# main.net
KiCad netlist of a schematic drawn in EAGLE
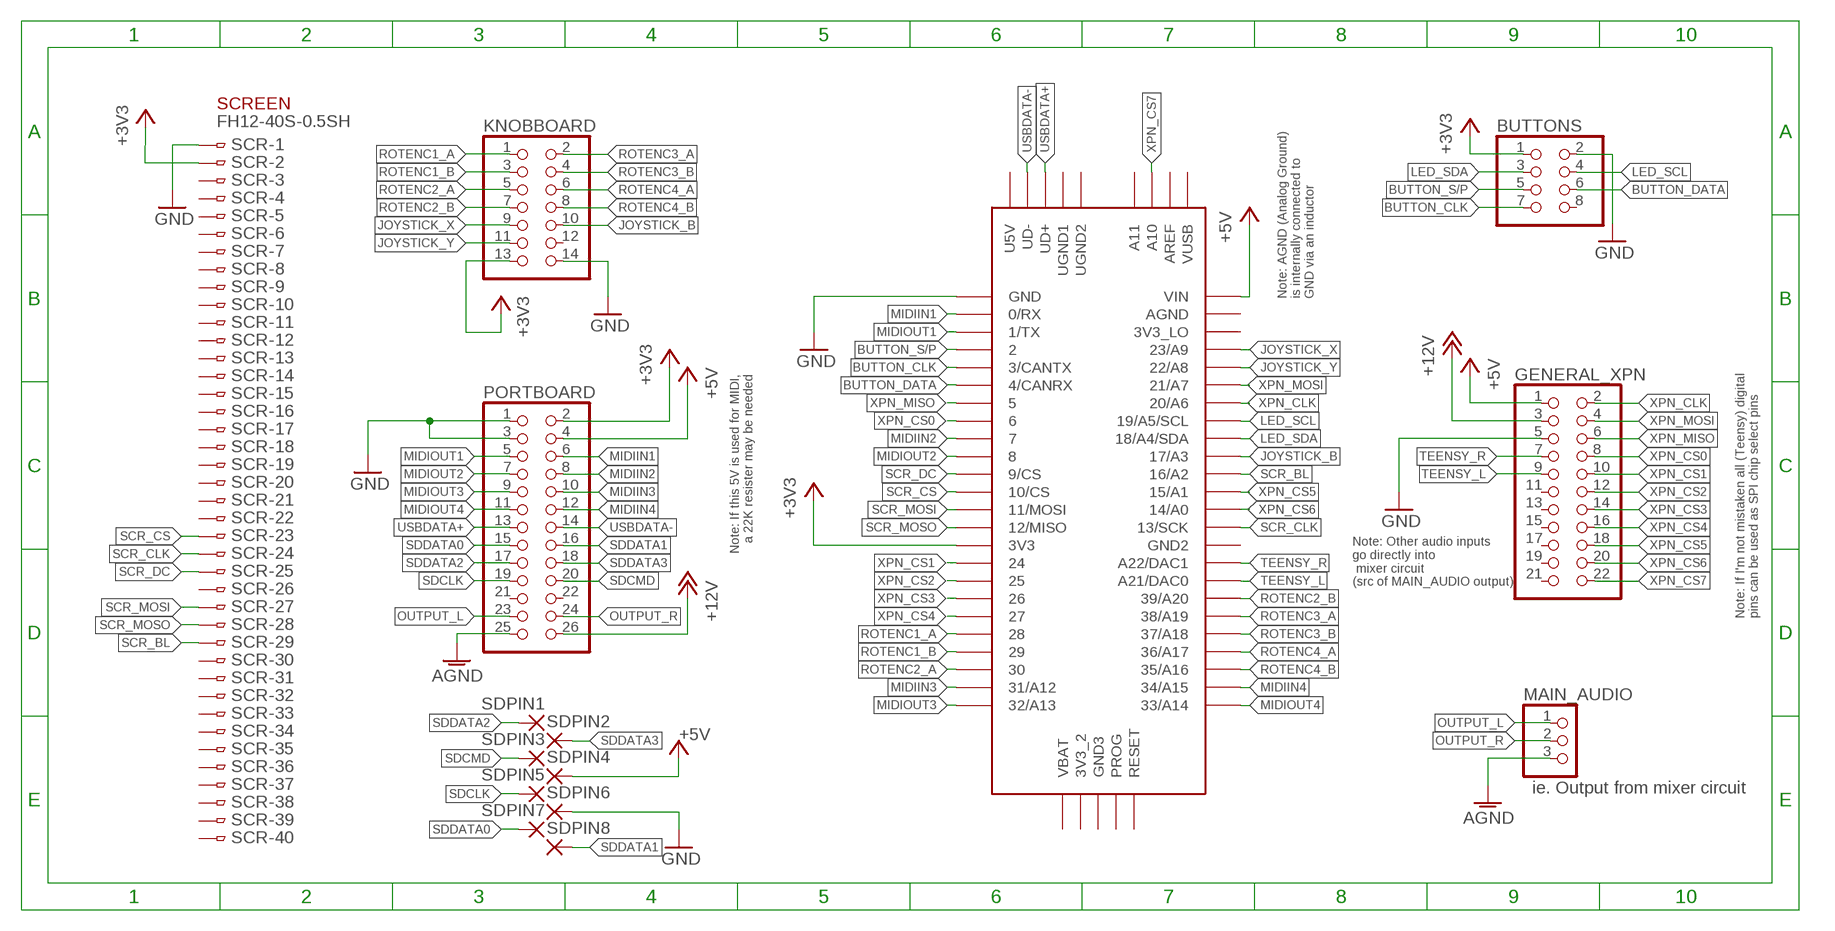
[diagram p0: schematic, sheet 1]

(export (version "E")
  (design (tool "Eeschema 10.0.6"))
  (components
    (comp (ref "BUTTONS")
      (value "PINHD-2X4")
      (footprint "eagle-import:2X04")
      (libsource (lib "eagle-import") (part "PINHD-2X4"))
    )
    (comp (ref "GENERAL_XPN")
      (value "PINHD-2X11")
      (footprint "eagle-import:2X11")
      (libsource (lib "eagle-import") (part "PINHD-2X11"))
    )
    (comp (ref "KNOBBOARD")
      (value "PINHD-2X7")
      (footprint "eagle-import:2X07")
      (libsource (lib "eagle-import") (part "PINHD-2X7"))
    )
    (comp (ref "MAIN_AUDIO")
      (value "PINHD-1X3")
      (footprint "eagle-import:1X03")
      (libsource (lib "eagle-import") (part "PINHD-1X3"))
    )
    (comp (ref "PORTBOARD")
      (value "PINHD-2X13")
      (footprint "eagle-import:2X13")
      (libsource (lib "eagle-import") (part "PINHD-2X13"))
    )
    (comp (ref "SCR")
      (value "FH12-40S-0.5SH")
      (footprint "eagle-import:FH12-40S-0.5SH")
      (fields (field (name "MPN") "FH12-40S-0.5SH(55)"))
      (libsource (lib "eagle-import") (part "FH12-40S-0.5SH"))
    )
    (comp (ref "SDPIN1")
      (value "1,6/0,8")
      (footprint "eagle-import:1,6_0,8")
      (libsource (lib "eagle-import") (part "1,6/0,8"))
    )
    (comp (ref "SDPIN2")
      (value "1,6/0,8")
      (footprint "eagle-import:1,6_0,8")
      (libsource (lib "eagle-import") (part "1,6/0,8"))
    )
    (comp (ref "SDPIN3")
      (value "1,6/0,8")
      (footprint "eagle-import:1,6_0,8")
      (libsource (lib "eagle-import") (part "1,6/0,8"))
    )
    (comp (ref "SDPIN4")
      (value "1,6/0,8")
      (footprint "eagle-import:1,6_0,8")
      (libsource (lib "eagle-import") (part "1,6/0,8"))
    )
    (comp (ref "SDPIN5")
      (value "1,6/0,8")
      (footprint "eagle-import:1,6_0,8")
      (libsource (lib "eagle-import") (part "1,6/0,8"))
    )
    (comp (ref "SDPIN6")
      (value "1,6/0,8")
      (footprint "eagle-import:1,6_0,8")
      (libsource (lib "eagle-import") (part "1,6/0,8"))
    )
    (comp (ref "SDPIN7")
      (value "1,6/0,8")
      (footprint "eagle-import:1,6_0,8")
      (libsource (lib "eagle-import") (part "1,6/0,8"))
    )
    (comp (ref "SDPIN8")
      (value "1,6/0,8")
      (footprint "eagle-import:1,6_0,8")
      (libsource (lib "eagle-import") (part "1,6/0,8"))
    )
    (comp (ref "TEENSY_3.6")
      (value "TEENSY_3.5/3.6")
      (footprint "eagle-import:TEENSY_3.5_3.6")
      (libsource (lib "eagle-import") (part "TEENSY_3.5/3.6"))
    )
  )
  (nets
    (net (code "1") (name "+3V3") (class "Default")
      (node (ref "BUTTONS") (pin "1") (pinfunction "1_1") (pintype "passive"))
      (node (ref "KNOBBOARD") (pin "13") (pinfunction "13_13") (pintype "passive"))
      (node (ref "PORTBOARD") (pin "2") (pinfunction "2_2") (pintype "passive"))
      (node (ref "SCR") (pin "2") (pinfunction "1_2") (pintype "passive"))
      (node (ref "TEENSY_3.6") (pin "3V3") (pinfunction "3V3_3V3") (pintype "bidirectional"))
    )
    (net (code "2") (name "+5V") (class "Default")
      (node (ref "GENERAL_XPN") (pin "1") (pinfunction "1_1") (pintype "passive"))
      (node (ref "PORTBOARD") (pin "4") (pinfunction "4_4") (pintype "passive"))
      (node (ref "SDPIN4") (pin "1") (pinfunction "P_1") (pintype "passive"))
      (node (ref "TEENSY_3.6") (pin "VIN") (pinfunction "VIN_VIN") (pintype "bidirectional"))
    )
    (net (code "3") (name "+12V") (class "Default")
      (node (ref "GENERAL_XPN") (pin "3") (pinfunction "3_3") (pintype "passive"))
      (node (ref "PORTBOARD") (pin "26") (pinfunction "26_26") (pintype "passive"))
    )
    (net (code "4") (name "AGND") (class "Default")
      (node (ref "MAIN_AUDIO") (pin "3") (pinfunction "3_3") (pintype "passive"))
      (node (ref "PORTBOARD") (pin "25") (pinfunction "25_25") (pintype "passive"))
    )
    (net (code "5") (name "BUTTON_CLK") (class "Default")
      (node (ref "BUTTONS") (pin "7") (pinfunction "7_7") (pintype "passive"))
      (node (ref "TEENSY_3.6") (pin "3/CANTX") (pinfunction "3/CANTX_3/CANTX") (pintype "bidirectional"))
    )
    (net (code "6") (name "BUTTON_DATA") (class "Default")
      (node (ref "BUTTONS") (pin "6") (pinfunction "6_6") (pintype "passive"))
      (node (ref "TEENSY_3.6") (pin "4/CANRX") (pinfunction "4/CANRX_4/CANRX") (pintype "bidirectional"))
    )
    (net (code "7") (name "BUTTON_S{slash}P") (class "Default")
      (node (ref "BUTTONS") (pin "5") (pinfunction "5_5") (pintype "passive"))
      (node (ref "TEENSY_3.6") (pin "2") (pinfunction "2_2") (pintype "bidirectional"))
    )
    (net (code "8") (name "GND") (class "Default")
      (node (ref "BUTTONS") (pin "2") (pinfunction "2_2") (pintype "passive"))
      (node (ref "GENERAL_XPN") (pin "5") (pinfunction "5_5") (pintype "passive"))
      (node (ref "KNOBBOARD") (pin "14") (pinfunction "14_14") (pintype "passive"))
      (node (ref "PORTBOARD") (pin "1") (pinfunction "1_1") (pintype "passive"))
      (node (ref "PORTBOARD") (pin "3") (pinfunction "3_3") (pintype "passive"))
      (node (ref "SCR") (pin "1") (pinfunction "1_1") (pintype "passive"))
      (node (ref "SDPIN6") (pin "1") (pinfunction "P_1") (pintype "passive"))
      (node (ref "TEENSY_3.6") (pin "GND") (pinfunction "GND_GND") (pintype "bidirectional"))
    )
    (net (code "9") (name "JOYSTICK_B") (class "Default")
      (node (ref "KNOBBOARD") (pin "10") (pinfunction "10_10") (pintype "passive"))
      (node (ref "TEENSY_3.6") (pin "17/A3") (pinfunction "17/A3_17/A3") (pintype "bidirectional"))
    )
    (net (code "10") (name "JOYSTICK_X") (class "Default")
      (node (ref "KNOBBOARD") (pin "9") (pinfunction "9_9") (pintype "passive"))
      (node (ref "TEENSY_3.6") (pin "23/A9") (pinfunction "23/A9_23/A9") (pintype "bidirectional"))
    )
    (net (code "11") (name "JOYSTICK_Y") (class "Default")
      (node (ref "KNOBBOARD") (pin "11") (pinfunction "11_11") (pintype "passive"))
      (node (ref "TEENSY_3.6") (pin "22/A8") (pinfunction "22/A8_22/A8") (pintype "bidirectional"))
    )
    (net (code "12") (name "LED_SCL") (class "Default")
      (node (ref "BUTTONS") (pin "4") (pinfunction "4_4") (pintype "passive"))
      (node (ref "TEENSY_3.6") (pin "19/A5/SCL") (pinfunction "19/A5/SCL_19/A5/SCL") (pintype "bidirectional"))
    )
    (net (code "13") (name "LED_SDA") (class "Default")
      (node (ref "BUTTONS") (pin "3") (pinfunction "3_3") (pintype "passive"))
      (node (ref "TEENSY_3.6") (pin "18/A4/SDA") (pinfunction "18/A4/SDA_18/A4/SDA") (pintype "bidirectional"))
    )
    (net (code "14") (name "MIDIIN1") (class "Default")
      (node (ref "PORTBOARD") (pin "6") (pinfunction "6_6") (pintype "passive"))
      (node (ref "TEENSY_3.6") (pin "0/RX") (pinfunction "0/RX_0/RX") (pintype "bidirectional"))
    )
    (net (code "15") (name "MIDIIN2") (class "Default")
      (node (ref "PORTBOARD") (pin "8") (pinfunction "8_8") (pintype "passive"))
      (node (ref "TEENSY_3.6") (pin "7") (pinfunction "7_7") (pintype "bidirectional"))
    )
    (net (code "16") (name "MIDIIN3") (class "Default")
      (node (ref "PORTBOARD") (pin "10") (pinfunction "10_10") (pintype "passive"))
      (node (ref "TEENSY_3.6") (pin "31/A12") (pinfunction "31/A12_31/A12") (pintype "bidirectional"))
    )
    (net (code "17") (name "MIDIIN4") (class "Default")
      (node (ref "PORTBOARD") (pin "12") (pinfunction "12_12") (pintype "passive"))
      (node (ref "TEENSY_3.6") (pin "34/A15") (pinfunction "34/A15_34/A15") (pintype "bidirectional"))
    )
    (net (code "18") (name "MIDIOUT1") (class "Default")
      (node (ref "PORTBOARD") (pin "5") (pinfunction "5_5") (pintype "passive"))
      (node (ref "TEENSY_3.6") (pin "1/TX") (pinfunction "1/TX_1/TX") (pintype "bidirectional"))
    )
    (net (code "19") (name "MIDIOUT2") (class "Default")
      (node (ref "PORTBOARD") (pin "7") (pinfunction "7_7") (pintype "passive"))
      (node (ref "TEENSY_3.6") (pin "8") (pinfunction "8_8") (pintype "bidirectional"))
    )
    (net (code "20") (name "MIDIOUT3") (class "Default")
      (node (ref "PORTBOARD") (pin "9") (pinfunction "9_9") (pintype "passive"))
      (node (ref "TEENSY_3.6") (pin "32/A13") (pinfunction "32/A13_32/A13") (pintype "bidirectional"))
    )
    (net (code "21") (name "MIDIOUT4") (class "Default")
      (node (ref "PORTBOARD") (pin "11") (pinfunction "11_11") (pintype "passive"))
      (node (ref "TEENSY_3.6") (pin "33/A14") (pinfunction "33/A14_33/A14") (pintype "bidirectional"))
    )
    (net (code "22") (name "OUTPUT_L") (class "Default")
      (node (ref "MAIN_AUDIO") (pin "1") (pinfunction "1_1") (pintype "passive"))
      (node (ref "PORTBOARD") (pin "23") (pinfunction "23_23") (pintype "passive"))
    )
    (net (code "23") (name "OUTPUT_R") (class "Default")
      (node (ref "MAIN_AUDIO") (pin "2") (pinfunction "2_2") (pintype "passive"))
      (node (ref "PORTBOARD") (pin "24") (pinfunction "24_24") (pintype "passive"))
    )
    (net (code "24") (name "ROTENC1_A") (class "Default")
      (node (ref "KNOBBOARD") (pin "1") (pinfunction "1_1") (pintype "passive"))
      (node (ref "TEENSY_3.6") (pin "28") (pinfunction "28_28") (pintype "bidirectional"))
    )
    (net (code "25") (name "ROTENC1_B") (class "Default")
      (node (ref "KNOBBOARD") (pin "3") (pinfunction "3_3") (pintype "passive"))
      (node (ref "TEENSY_3.6") (pin "29") (pinfunction "29_29") (pintype "bidirectional"))
    )
    (net (code "26") (name "ROTENC2_A") (class "Default")
      (node (ref "KNOBBOARD") (pin "5") (pinfunction "5_5") (pintype "passive"))
      (node (ref "TEENSY_3.6") (pin "30") (pinfunction "30_30") (pintype "bidirectional"))
    )
    (net (code "27") (name "ROTENC2_B") (class "Default")
      (node (ref "KNOBBOARD") (pin "7") (pinfunction "7_7") (pintype "passive"))
      (node (ref "TEENSY_3.6") (pin "39/A20") (pinfunction "39/A20_39/A20") (pintype "bidirectional"))
    )
    (net (code "28") (name "ROTENC3_A") (class "Default")
      (node (ref "KNOBBOARD") (pin "2") (pinfunction "2_2") (pintype "passive"))
      (node (ref "TEENSY_3.6") (pin "38/A19") (pinfunction "38/A19_38/A19") (pintype "bidirectional"))
    )
    (net (code "29") (name "ROTENC3_B") (class "Default")
      (node (ref "KNOBBOARD") (pin "4") (pinfunction "4_4") (pintype "passive"))
      (node (ref "TEENSY_3.6") (pin "37/A18") (pinfunction "37/A18_37/A18") (pintype "bidirectional"))
    )
    (net (code "30") (name "ROTENC4_A") (class "Default")
      (node (ref "KNOBBOARD") (pin "6") (pinfunction "6_6") (pintype "passive"))
      (node (ref "TEENSY_3.6") (pin "36/A17") (pinfunction "36/A17_36/A17") (pintype "bidirectional"))
    )
    (net (code "31") (name "ROTENC4_B") (class "Default")
      (node (ref "KNOBBOARD") (pin "8") (pinfunction "8_8") (pintype "passive"))
      (node (ref "TEENSY_3.6") (pin "35/A16") (pinfunction "35/A16_35/A16") (pintype "bidirectional"))
    )
    (net (code "32") (name "SCR_BL") (class "Default")
      (node (ref "SCR") (pin "29") (pinfunction "1_29") (pintype "passive"))
      (node (ref "TEENSY_3.6") (pin "16/A2") (pinfunction "16/A2_16/A2") (pintype "bidirectional"))
    )
    (net (code "33") (name "SCR_CLK") (class "Default")
      (node (ref "SCR") (pin "24") (pinfunction "1_24") (pintype "passive"))
      (node (ref "TEENSY_3.6") (pin "13/SCK") (pinfunction "13/SCK_13/SCK") (pintype "bidirectional"))
    )
    (net (code "34") (name "SCR_CS") (class "Default")
      (node (ref "SCR") (pin "23") (pinfunction "1_23") (pintype "passive"))
      (node (ref "TEENSY_3.6") (pin "10/CS") (pinfunction "10/CS_10/CS") (pintype "bidirectional"))
    )
    (net (code "35") (name "SCR_DC") (class "Default")
      (node (ref "SCR") (pin "25") (pinfunction "1_25") (pintype "passive"))
      (node (ref "TEENSY_3.6") (pin "9/CS") (pinfunction "9/CS_9/CS") (pintype "bidirectional"))
    )
    (net (code "36") (name "SCR_MOSI") (class "Default")
      (node (ref "SCR") (pin "27") (pinfunction "1_27") (pintype "passive"))
      (node (ref "TEENSY_3.6") (pin "11/MOSI") (pinfunction "11/MOSI_11/MOSI") (pintype "bidirectional"))
    )
    (net (code "37") (name "SCR_MOSO") (class "Default")
      (node (ref "SCR") (pin "28") (pinfunction "1_28") (pintype "passive"))
      (node (ref "TEENSY_3.6") (pin "12/MISO") (pinfunction "12/MISO_12/MISO") (pintype "bidirectional"))
    )
    (net (code "38") (name "SDCLK") (class "Default")
      (node (ref "PORTBOARD") (pin "19") (pinfunction "19_19") (pintype "passive"))
      (node (ref "SDPIN5") (pin "1") (pinfunction "P_1") (pintype "passive"))
    )
    (net (code "39") (name "SDCMD") (class "Default")
      (node (ref "PORTBOARD") (pin "20") (pinfunction "20_20") (pintype "passive"))
      (node (ref "SDPIN3") (pin "1") (pinfunction "P_1") (pintype "passive"))
    )
    (net (code "40") (name "SDDATA0") (class "Default")
      (node (ref "PORTBOARD") (pin "15") (pinfunction "15_15") (pintype "passive"))
      (node (ref "SDPIN7") (pin "1") (pinfunction "P_1") (pintype "passive"))
    )
    (net (code "41") (name "SDDATA1") (class "Default")
      (node (ref "PORTBOARD") (pin "16") (pinfunction "16_16") (pintype "passive"))
      (node (ref "SDPIN8") (pin "1") (pinfunction "P_1") (pintype "passive"))
    )
    (net (code "42") (name "SDDATA2") (class "Default")
      (node (ref "PORTBOARD") (pin "17") (pinfunction "17_17") (pintype "passive"))
      (node (ref "SDPIN1") (pin "1") (pinfunction "P_1") (pintype "passive"))
    )
    (net (code "43") (name "SDDATA3") (class "Default")
      (node (ref "PORTBOARD") (pin "18") (pinfunction "18_18") (pintype "passive"))
      (node (ref "SDPIN2") (pin "1") (pinfunction "P_1") (pintype "passive"))
    )
    (net (code "44") (name "TEENSY_L") (class "Default")
      (node (ref "GENERAL_XPN") (pin "9") (pinfunction "9_9") (pintype "passive"))
      (node (ref "TEENSY_3.6") (pin "21/DAC0") (pinfunction "A21/DAC0_21/DAC0") (pintype "bidirectional"))
    )
    (net (code "45") (name "TEENSY_R") (class "Default")
      (node (ref "GENERAL_XPN") (pin "7") (pinfunction "7_7") (pintype "passive"))
      (node (ref "TEENSY_3.6") (pin "A22/DAC1") (pinfunction "A22/DAC1_A22/DAC1") (pintype "bidirectional"))
    )
    (net (code "46") (name "USBDATA+") (class "Default")
      (node (ref "PORTBOARD") (pin "13") (pinfunction "13_13") (pintype "passive"))
      (node (ref "TEENSY_3.6") (pin "UD+") (pinfunction "UD+_UD+") (pintype "bidirectional"))
    )
    (net (code "47") (name "USBDATA-") (class "Default")
      (node (ref "PORTBOARD") (pin "14") (pinfunction "14_14") (pintype "passive"))
      (node (ref "TEENSY_3.6") (pin "UD-") (pinfunction "UD-_UD-") (pintype "bidirectional"))
    )
    (net (code "48") (name "XPN_CLK") (class "Default")
      (node (ref "GENERAL_XPN") (pin "2") (pinfunction "2_2") (pintype "passive"))
      (node (ref "TEENSY_3.6") (pin "20/A6") (pinfunction "20/A6_20/A6") (pintype "bidirectional"))
    )
    (net (code "49") (name "XPN_CS0") (class "Default")
      (node (ref "GENERAL_XPN") (pin "8") (pinfunction "8_8") (pintype "passive"))
      (node (ref "TEENSY_3.6") (pin "6") (pinfunction "6_6") (pintype "bidirectional"))
    )
    (net (code "50") (name "XPN_CS1") (class "Default")
      (node (ref "GENERAL_XPN") (pin "10") (pinfunction "10_10") (pintype "passive"))
      (node (ref "TEENSY_3.6") (pin "24") (pinfunction "24_24") (pintype "bidirectional"))
    )
    (net (code "51") (name "XPN_CS2") (class "Default")
      (node (ref "GENERAL_XPN") (pin "12") (pinfunction "12_12") (pintype "passive"))
      (node (ref "TEENSY_3.6") (pin "25") (pinfunction "25_25") (pintype "bidirectional"))
    )
    (net (code "52") (name "XPN_CS3") (class "Default")
      (node (ref "GENERAL_XPN") (pin "14") (pinfunction "14_14") (pintype "passive"))
      (node (ref "TEENSY_3.6") (pin "26") (pinfunction "26_26") (pintype "bidirectional"))
    )
    (net (code "53") (name "XPN_CS4") (class "Default")
      (node (ref "GENERAL_XPN") (pin "16") (pinfunction "16_16") (pintype "passive"))
      (node (ref "TEENSY_3.6") (pin "27") (pinfunction "27_27") (pintype "bidirectional"))
    )
    (net (code "54") (name "XPN_CS5") (class "Default")
      (node (ref "GENERAL_XPN") (pin "18") (pinfunction "18_18") (pintype "passive"))
      (node (ref "TEENSY_3.6") (pin "15/A1") (pinfunction "15/A1_15/A1") (pintype "bidirectional"))
    )
    (net (code "55") (name "XPN_CS6") (class "Default")
      (node (ref "GENERAL_XPN") (pin "20") (pinfunction "20_20") (pintype "passive"))
      (node (ref "TEENSY_3.6") (pin "14/A0") (pinfunction "14/A0_14/A0") (pintype "bidirectional"))
    )
    (net (code "56") (name "XPN_CS7") (class "Default")
      (node (ref "GENERAL_XPN") (pin "22") (pinfunction "22_22") (pintype "passive"))
      (node (ref "TEENSY_3.6") (pin "A10") (pinfunction "A10_A10") (pintype "bidirectional"))
    )
    (net (code "57") (name "XPN_MISO") (class "Default")
      (node (ref "GENERAL_XPN") (pin "6") (pinfunction "6_6") (pintype "passive"))
      (node (ref "TEENSY_3.6") (pin "5") (pinfunction "5_5") (pintype "bidirectional"))
    )
    (net (code "58") (name "XPN_MOSI") (class "Default")
      (node (ref "GENERAL_XPN") (pin "4") (pinfunction "4_4") (pintype "passive"))
      (node (ref "TEENSY_3.6") (pin "21/A7") (pinfunction "21/A7_21/A7") (pintype "bidirectional"))
    )
    (net (code "59") (name "unconnected-(BUTTONS-Pad8)") (class "Default")
      (node (ref "BUTTONS") (pin "8") (pinfunction "8_8") (pintype "passive"))
    )
    (net (code "60") (name "unconnected-(GENERAL_XPN-Pad11)") (class "Default")
      (node (ref "GENERAL_XPN") (pin "11") (pinfunction "11_11") (pintype "passive"))
    )
    (net (code "61") (name "unconnected-(GENERAL_XPN-Pad13)") (class "Default")
      (node (ref "GENERAL_XPN") (pin "13") (pinfunction "13_13") (pintype "passive"))
    )
    (net (code "62") (name "unconnected-(GENERAL_XPN-Pad15)") (class "Default")
      (node (ref "GENERAL_XPN") (pin "15") (pinfunction "15_15") (pintype "passive"))
    )
    (net (code "63") (name "unconnected-(GENERAL_XPN-Pad17)") (class "Default")
      (node (ref "GENERAL_XPN") (pin "17") (pinfunction "17_17") (pintype "passive"))
    )
    (net (code "64") (name "unconnected-(GENERAL_XPN-Pad19)") (class "Default")
      (node (ref "GENERAL_XPN") (pin "19") (pinfunction "19_19") (pintype "passive"))
    )
    (net (code "65") (name "unconnected-(GENERAL_XPN-Pad21)") (class "Default")
      (node (ref "GENERAL_XPN") (pin "21") (pinfunction "21_21") (pintype "passive"))
    )
    (net (code "66") (name "unconnected-(KNOBBOARD-Pad12)") (class "Default")
      (node (ref "KNOBBOARD") (pin "12") (pinfunction "12_12") (pintype "passive"))
    )
    (net (code "67") (name "unconnected-(PORTBOARD-Pad21)") (class "Default")
      (node (ref "PORTBOARD") (pin "21") (pinfunction "21_21") (pintype "passive"))
    )
    (net (code "68") (name "unconnected-(PORTBOARD-Pad22)") (class "Default")
      (node (ref "PORTBOARD") (pin "22") (pinfunction "22_22") (pintype "passive"))
    )
    (net (code "69") (name "unconnected-(SCRAA-1-Pad33)") (class "Default")
      (node (ref "SCR") (pin "33") (pinfunction "1_33") (pintype "passive"))
    )
    (net (code "70") (name "unconnected-(SCRAB-1-Pad34)") (class "Default")
      (node (ref "SCR") (pin "34") (pinfunction "1_34") (pintype "passive"))
    )
    (net (code "71") (name "unconnected-(SCRAC-1-Pad35)") (class "Default")
      (node (ref "SCR") (pin "35") (pinfunction "1_35") (pintype "passive"))
    )
    (net (code "72") (name "unconnected-(SCRAD-1-Pad36)") (class "Default")
      (node (ref "SCR") (pin "36") (pinfunction "1_36") (pintype "passive"))
    )
    (net (code "73") (name "unconnected-(SCRAE-1-Pad37)") (class "Default")
      (node (ref "SCR") (pin "37") (pinfunction "1_37") (pintype "passive"))
    )
    (net (code "74") (name "unconnected-(SCRAF-1-Pad38)") (class "Default")
      (node (ref "SCR") (pin "38") (pinfunction "1_38") (pintype "passive"))
    )
    (net (code "75") (name "unconnected-(SCRAG-1-Pad39)") (class "Default")
      (node (ref "SCR") (pin "39") (pinfunction "1_39") (pintype "passive"))
    )
    (net (code "76") (name "unconnected-(SCRAH-1-Pad4)") (class "Default")
      (node (ref "SCR") (pin "4") (pinfunction "1_4") (pintype "passive"))
    )
    (net (code "77") (name "unconnected-(SCRAI-1-Pad40)") (class "Default")
      (node (ref "SCR") (pin "40") (pinfunction "1_40") (pintype "passive"))
    )
    (net (code "78") (name "unconnected-(SCRAJ-1-Pad5)") (class "Default")
      (node (ref "SCR") (pin "5") (pinfunction "1_5") (pintype "passive"))
    )
    (net (code "79") (name "unconnected-(SCRAK-1-Pad6)") (class "Default")
      (node (ref "SCR") (pin "6") (pinfunction "1_6") (pintype "passive"))
    )
    (net (code "80") (name "unconnected-(SCRAL-1-Pad7)") (class "Default")
      (node (ref "SCR") (pin "7") (pinfunction "1_7") (pintype "passive"))
    )
    (net (code "81") (name "unconnected-(SCRAM-1-Pad8)") (class "Default")
      (node (ref "SCR") (pin "8") (pinfunction "1_8") (pintype "passive"))
    )
    (net (code "82") (name "unconnected-(SCRAN-1-Pad9)") (class "Default")
      (node (ref "SCR") (pin "9") (pinfunction "1_9") (pintype "passive"))
    )
    (net (code "83") (name "unconnected-(SCRB-1-Pad10)") (class "Default")
      (node (ref "SCR") (pin "10") (pinfunction "1_10") (pintype "passive"))
    )
    (net (code "84") (name "unconnected-(SCRC-1-Pad11)") (class "Default")
      (node (ref "SCR") (pin "11") (pinfunction "1_11") (pintype "passive"))
    )
    (net (code "85") (name "unconnected-(SCRD-1-Pad12)") (class "Default")
      (node (ref "SCR") (pin "12") (pinfunction "1_12") (pintype "passive"))
    )
    (net (code "86") (name "unconnected-(SCRE-1-Pad13)") (class "Default")
      (node (ref "SCR") (pin "13") (pinfunction "1_13") (pintype "passive"))
    )
    (net (code "87") (name "unconnected-(SCRF-1-Pad14)") (class "Default")
      (node (ref "SCR") (pin "14") (pinfunction "1_14") (pintype "passive"))
    )
    (net (code "88") (name "unconnected-(SCRG-1-Pad15)") (class "Default")
      (node (ref "SCR") (pin "15") (pinfunction "1_15") (pintype "passive"))
    )
    (net (code "89") (name "unconnected-(SCRH-1-Pad16)") (class "Default")
      (node (ref "SCR") (pin "16") (pinfunction "1_16") (pintype "passive"))
    )
    (net (code "90") (name "unconnected-(SCRI-1-Pad17)") (class "Default")
      (node (ref "SCR") (pin "17") (pinfunction "1_17") (pintype "passive"))
    )
    (net (code "91") (name "unconnected-(SCRJ-1-Pad18)") (class "Default")
      (node (ref "SCR") (pin "18") (pinfunction "1_18") (pintype "passive"))
    )
    (net (code "92") (name "unconnected-(SCRK-1-Pad19)") (class "Default")
      (node (ref "SCR") (pin "19") (pinfunction "1_19") (pintype "passive"))
    )
    (net (code "93") (name "unconnected-(SCRM-1-Pad20)") (class "Default")
      (node (ref "SCR") (pin "20") (pinfunction "1_20") (pintype "passive"))
    )
    (net (code "94") (name "unconnected-(SCRN-1-Pad21)") (class "Default")
      (node (ref "SCR") (pin "21") (pinfunction "1_21") (pintype "passive"))
    )
    (net (code "95") (name "unconnected-(SCRO-1-Pad22)") (class "Default")
      (node (ref "SCR") (pin "22") (pinfunction "1_22") (pintype "passive"))
    )
    (net (code "96") (name "unconnected-(SCRS-1-Pad26)") (class "Default")
      (node (ref "SCR") (pin "26") (pinfunction "1_26") (pintype "passive"))
    )
    (net (code "97") (name "unconnected-(SCRW-1-Pad3)") (class "Default")
      (node (ref "SCR") (pin "3") (pinfunction "1_3") (pintype "passive"))
    )
    (net (code "98") (name "unconnected-(SCRX-1-Pad30)") (class "Default")
      (node (ref "SCR") (pin "30") (pinfunction "1_30") (pintype "passive"))
    )
    (net (code "99") (name "unconnected-(SCRY-1-Pad31)") (class "Default")
      (node (ref "SCR") (pin "31") (pinfunction "1_31") (pintype "passive"))
    )
    (net (code "100") (name "unconnected-(SCRZ-1-Pad32)") (class "Default")
      (node (ref "SCR") (pin "32") (pinfunction "1_32") (pintype "passive"))
    )
    (net (code "101") (name "unconnected-(TEENSY_3.6-Pad3V3_2)") (class "Default")
      (node (ref "TEENSY_3.6") (pin "3V3_2") (pinfunction "3V3_2_3V3_2") (pintype "bidirectional"))
    )
    (net (code "102") (name "unconnected-(TEENSY_3.6-Pad3V3_LO)") (class "Default")
      (node (ref "TEENSY_3.6") (pin "3V3_LO") (pinfunction "3V3_LO_3V3_LO") (pintype "bidirectional"))
    )
    (net (code "103") (name "unconnected-(TEENSY_3.6-PadA11)") (class "Default")
      (node (ref "TEENSY_3.6") (pin "A11") (pinfunction "A11_A11") (pintype "bidirectional"))
    )
    (net (code "104") (name "unconnected-(TEENSY_3.6-PadAGND)") (class "Default")
      (node (ref "TEENSY_3.6") (pin "AGND") (pinfunction "AGND_AGND") (pintype "bidirectional"))
    )
    (net (code "105") (name "unconnected-(TEENSY_3.6-PadAREF)") (class "Default")
      (node (ref "TEENSY_3.6") (pin "AREF") (pinfunction "AREF_AREF") (pintype "bidirectional"))
    )
    (net (code "106") (name "unconnected-(TEENSY_3.6-PadGND2)") (class "Default")
      (node (ref "TEENSY_3.6") (pin "GND2") (pinfunction "GND2_GND2") (pintype "bidirectional"))
    )
    (net (code "107") (name "unconnected-(TEENSY_3.6-PadGND3)") (class "Default")
      (node (ref "TEENSY_3.6") (pin "GND3") (pinfunction "GND3_GND3") (pintype "bidirectional"))
    )
    (net (code "108") (name "unconnected-(TEENSY_3.6-PadPROG)") (class "Default")
      (node (ref "TEENSY_3.6") (pin "PROG") (pinfunction "PROG_PROG") (pintype "bidirectional"))
    )
    (net (code "109") (name "unconnected-(TEENSY_3.6-PadRESET)") (class "Default")
      (node (ref "TEENSY_3.6") (pin "RESET") (pinfunction "RESET_RESET") (pintype "bidirectional"))
    )
    (net (code "110") (name "unconnected-(TEENSY_3.6-PadU5V)") (class "Default")
      (node (ref "TEENSY_3.6") (pin "U5V") (pinfunction "U5V_U5V") (pintype "bidirectional"))
    )
    (net (code "111") (name "unconnected-(TEENSY_3.6-PadUGND1)") (class "Default")
      (node (ref "TEENSY_3.6") (pin "UGND1") (pinfunction "UGND1_UGND1") (pintype "bidirectional"))
    )
    (net (code "112") (name "unconnected-(TEENSY_3.6-PadUGND2)") (class "Default")
      (node (ref "TEENSY_3.6") (pin "UGND2") (pinfunction "UGND2_UGND2") (pintype "bidirectional"))
    )
    (net (code "113") (name "unconnected-(TEENSY_3.6-PadVBAT)") (class "Default")
      (node (ref "TEENSY_3.6") (pin "VBAT") (pinfunction "VBAT_VBAT") (pintype "bidirectional"))
    )
    (net (code "114") (name "unconnected-(TEENSY_3.6-PadVUSB)") (class "Default")
      (node (ref "TEENSY_3.6") (pin "VUSB") (pinfunction "VUSB_VUSB") (pintype "bidirectional"))
    )
  )
)
